# 14_BTB.net
KiCad netlist of a schematic drawn in Altium Designer
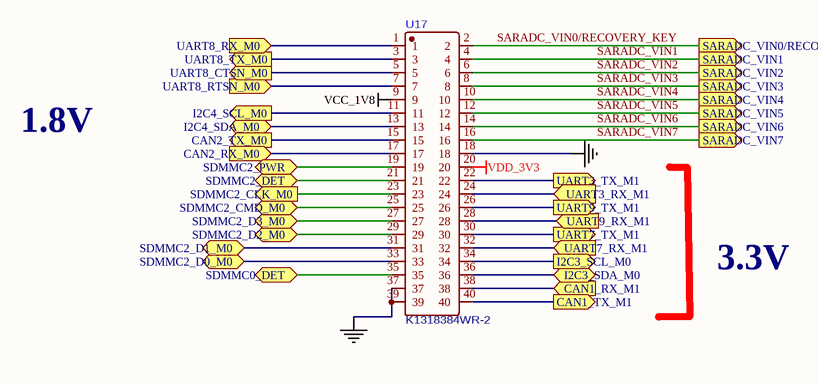
[diagram p0: 14_BTB连接器.schdoc]

(export (version "E")
  (design (tool "Eeschema 10.0.6"))
  (components
    (comp (ref "U17")
      (value "K1318384WR-2")
      (footprint "CONN-TH_K1318384WR-2")
      (description "排针")
      (libsource (lib "RK3568核心板") (part "K1318384WR-2"))
    )
  )
  (nets
    (net (code "1") (name "/CAN1_RX_M1") (class "Default")
      (node (ref "U17") (pin "38") (pinfunction "38_38") (pintype "passive"))
    )
    (net (code "2") (name "/CAN1_TX_M1") (class "Default")
      (node (ref "U17") (pin "40") (pinfunction "40_40") (pintype "passive"))
    )
    (net (code "3") (name "/CAN2_RX_M0") (class "Default")
      (node (ref "U17") (pin "17") (pinfunction "17_17") (pintype "passive"))
    )
    (net (code "4") (name "/CAN2_TX_M0") (class "Default")
      (node (ref "U17") (pin "15") (pinfunction "15_15") (pintype "passive"))
    )
    (net (code "5") (name "/I2C3_SCL_M0") (class "Default")
      (node (ref "U17") (pin "34") (pinfunction "34_34") (pintype "passive"))
    )
    (net (code "6") (name "/I2C3_SDA_M0") (class "Default")
      (node (ref "U17") (pin "36") (pinfunction "36_36") (pintype "passive"))
    )
    (net (code "7") (name "/I2C4_SCL_M0") (class "Default")
      (node (ref "U17") (pin "11") (pinfunction "11_11") (pintype "passive"))
    )
    (net (code "8") (name "/I2C4_SDA_M0") (class "Default")
      (node (ref "U17") (pin "13") (pinfunction "13_13") (pintype "passive"))
    )
    (net (code "9") (name "/SARADC_VIN0{slash}RECOVERY_KEY") (class "Default")
      (node (ref "U17") (pin "2") (pinfunction "2_2") (pintype "passive"))
    )
    (net (code "10") (name "/SARADC_VIN1") (class "Default")
      (node (ref "U17") (pin "4") (pinfunction "4_4") (pintype "passive"))
    )
    (net (code "11") (name "/SARADC_VIN2") (class "Default")
      (node (ref "U17") (pin "6") (pinfunction "6_6") (pintype "passive"))
    )
    (net (code "12") (name "/SARADC_VIN3") (class "Default")
      (node (ref "U17") (pin "8") (pinfunction "8_8") (pintype "passive"))
    )
    (net (code "13") (name "/SARADC_VIN4") (class "Default")
      (node (ref "U17") (pin "10") (pinfunction "10_10") (pintype "passive"))
    )
    (net (code "14") (name "/SARADC_VIN5") (class "Default")
      (node (ref "U17") (pin "12") (pinfunction "12_12") (pintype "passive"))
    )
    (net (code "15") (name "/SARADC_VIN6") (class "Default")
      (node (ref "U17") (pin "14") (pinfunction "14_14") (pintype "passive"))
    )
    (net (code "16") (name "/SARADC_VIN7") (class "Default")
      (node (ref "U17") (pin "16") (pinfunction "16_16") (pintype "passive"))
    )
    (net (code "17") (name "/SDMMC0_DET") (class "Default")
      (node (ref "U17") (pin "35") (pinfunction "35_35") (pintype "passive"))
    )
    (net (code "18") (name "/SDMMC2_CLK_M0") (class "Default")
      (node (ref "U17") (pin "23") (pinfunction "23_23") (pintype "passive"))
    )
    (net (code "19") (name "/SDMMC2_CMD_M0") (class "Default")
      (node (ref "U17") (pin "25") (pinfunction "25_25") (pintype "passive"))
    )
    (net (code "20") (name "/SDMMC2_D0_M0") (class "Default")
      (node (ref "U17") (pin "33") (pinfunction "33_33") (pintype "passive"))
    )
    (net (code "21") (name "/SDMMC2_D1_M0") (class "Default")
      (node (ref "U17") (pin "31") (pinfunction "31_31") (pintype "passive"))
    )
    (net (code "22") (name "/SDMMC2_D2_M0") (class "Default")
      (node (ref "U17") (pin "29") (pinfunction "29_29") (pintype "passive"))
    )
    (net (code "23") (name "/SDMMC2_D3_M0") (class "Default")
      (node (ref "U17") (pin "27") (pinfunction "27_27") (pintype "passive"))
    )
    (net (code "24") (name "/SDMMC2_DET") (class "Default")
      (node (ref "U17") (pin "21") (pinfunction "21_21") (pintype "passive"))
    )
    (net (code "25") (name "/SDMMC2_PWR") (class "Default")
      (node (ref "U17") (pin "19") (pinfunction "19_19") (pintype "passive"))
    )
    (net (code "26") (name "/UART3_RX_M1") (class "Default")
      (node (ref "U17") (pin "24") (pinfunction "24_24") (pintype "passive"))
    )
    (net (code "27") (name "/UART3_TX_M1") (class "Default")
      (node (ref "U17") (pin "22") (pinfunction "22_22") (pintype "passive"))
    )
    (net (code "28") (name "/UART7_RX_M1") (class "Default")
      (node (ref "U17") (pin "32") (pinfunction "32_32") (pintype "passive"))
    )
    (net (code "29") (name "/UART7_TX_M1") (class "Default")
      (node (ref "U17") (pin "30") (pinfunction "30_30") (pintype "passive"))
    )
    (net (code "30") (name "/UART8_CTSN_M0") (class "Default")
      (node (ref "U17") (pin "5") (pinfunction "5_5") (pintype "passive"))
    )
    (net (code "31") (name "/UART8_RTSN_M0") (class "Default")
      (node (ref "U17") (pin "7") (pinfunction "7_7") (pintype "passive"))
    )
    (net (code "32") (name "/UART8_RX_M0") (class "Default")
      (node (ref "U17") (pin "1") (pinfunction "1_1") (pintype "passive"))
    )
    (net (code "33") (name "/UART8_TX_M0") (class "Default")
      (node (ref "U17") (pin "3") (pinfunction "3_3") (pintype "passive"))
    )
    (net (code "34") (name "/UART9_RX_M1") (class "Default")
      (node (ref "U17") (pin "28") (pinfunction "28_28") (pintype "passive"))
    )
    (net (code "35") (name "/UART9_TX_M1") (class "Default")
      (node (ref "U17") (pin "26") (pinfunction "26_26") (pintype "passive"))
    )
    (net (code "36") (name "GND") (class "Default")
      (node (ref "U17") (pin "18") (pinfunction "18_18") (pintype "passive"))
      (node (ref "U17") (pin "37") (pinfunction "37_37") (pintype "passive"))
      (node (ref "U17") (pin "39") (pinfunction "39_39") (pintype "passive"))
    )
    (net (code "37") (name "VCC_1V8") (class "Default")
      (node (ref "U17") (pin "9") (pinfunction "9_9") (pintype "passive"))
    )
    (net (code "38") (name "VDD_3V3") (class "Default")
      (node (ref "U17") (pin "20") (pinfunction "20_20") (pintype "passive"))
    )
  )
)
